# uoolight.net
KiCad netlist of a schematic drawn in EAGLE
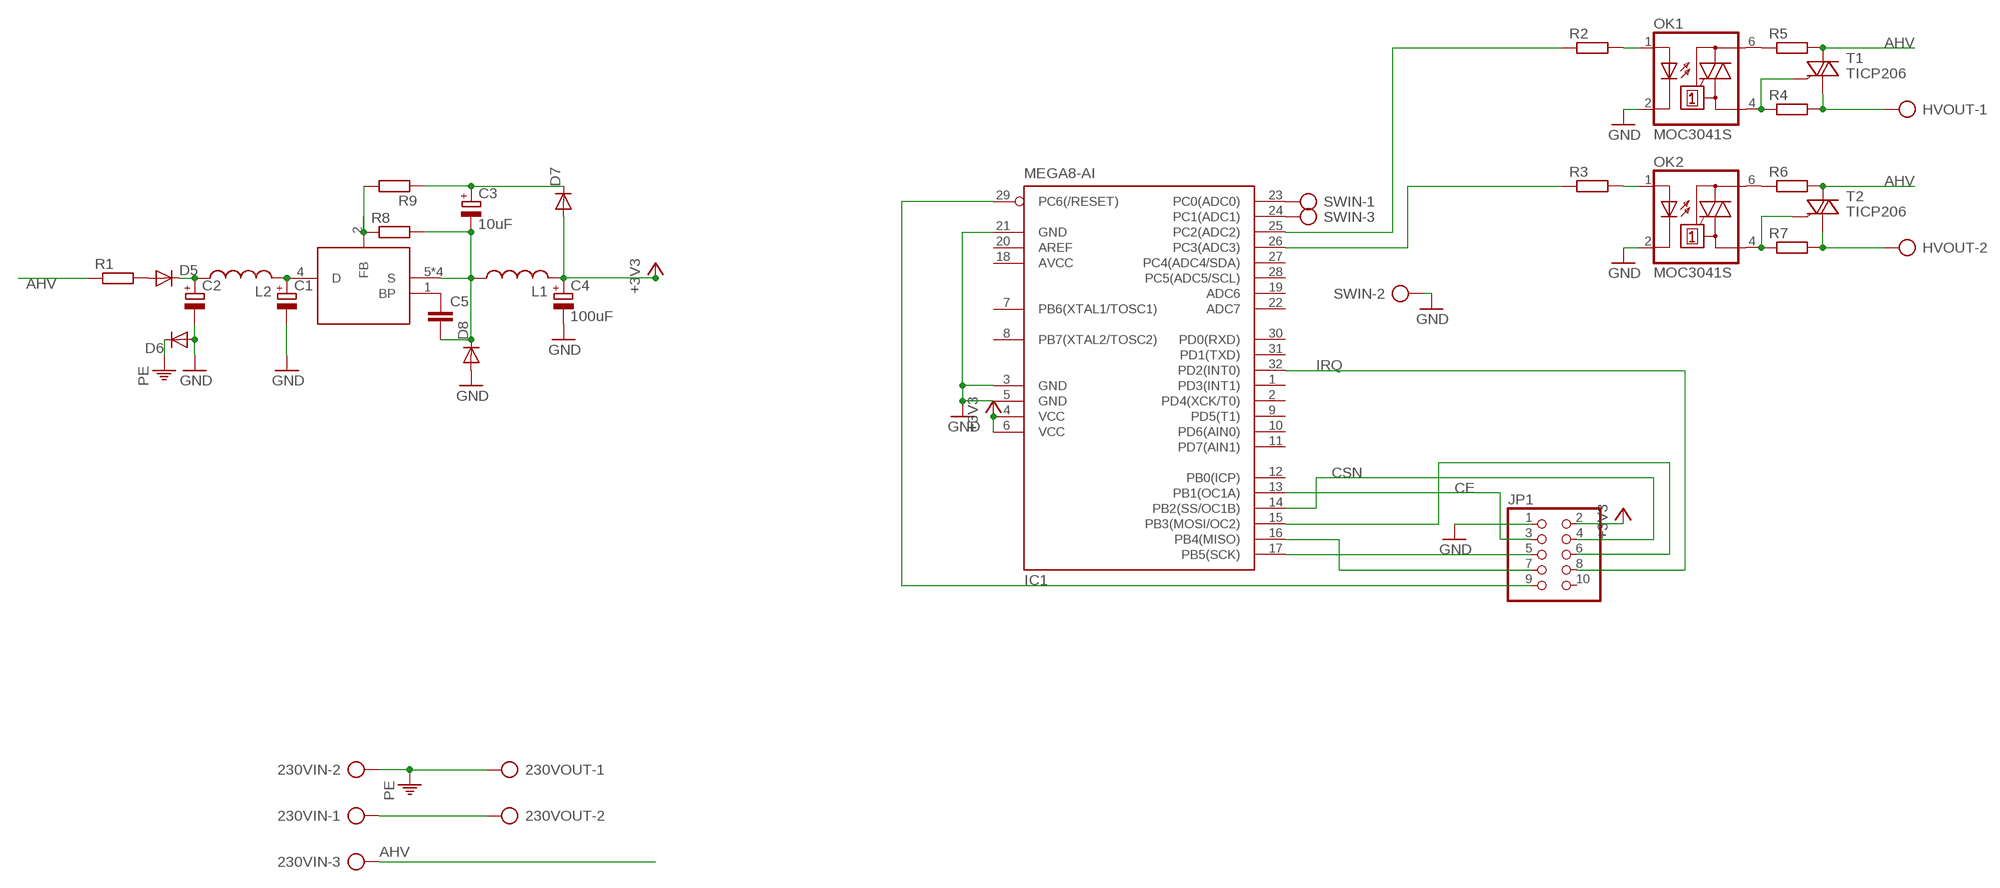
[diagram p0: schematic, sheet 1]

(export (version "E")
  (design (tool "Eeschema 10.0.6"))
  (components
    (comp (ref "230VIN")
      (value "AK500/3")
      (footprint "eagle-import:AK500_3")
      (libsource (lib "eagle-import") (part "AK500/3"))
    )
    (comp (ref "230VOUT")
      (value "AK500/2")
      (footprint "eagle-import:AK500_2")
      (libsource (lib "eagle-import") (part "AK500/2"))
    )
    (comp (ref "C1")
      (value "CPOL-EUE5-10.5")
      (footprint "eagle-import:E5-10,5")
      (libsource (lib "eagle-import") (part "CPOL-EUE5-10.5"))
    )
    (comp (ref "C2")
      (value "CPOL-EUE5-10.5")
      (footprint "eagle-import:E5-10,5")
      (libsource (lib "eagle-import") (part "CPOL-EUE5-10.5"))
    )
    (comp (ref "C3")
      (value "10uF")
      (footprint "eagle-import:153CLV-0505")
      (libsource (lib "eagle-import") (part "CPOL-EU153CLV-0505"))
    )
    (comp (ref "C4")
      (value "100uF")
      (footprint "eagle-import:153CLV-0605")
      (libsource (lib "eagle-import") (part "CPOL-EU153CLV-0605"))
    )
    (comp (ref "C5")
      (value "C-EUC0603K")
      (footprint "eagle-import:C0603K")
      (libsource (lib "eagle-import") (part "C-EUC0603K"))
    )
    (comp (ref "D5")
      (value "DIODE-SOD323-W")
      (footprint "eagle-import:SOD323-W")
      (libsource (lib "eagle-import") (part "DIODE-SOD323-W"))
    )
    (comp (ref "D6")
      (value "DIODE-SOD323-W")
      (footprint "eagle-import:SOD323-W")
      (libsource (lib "eagle-import") (part "DIODE-SOD323-W"))
    )
    (comp (ref "D7")
      (value "DIODE-SOD323-W")
      (footprint "eagle-import:SOD323-W")
      (libsource (lib "eagle-import") (part "DIODE-SOD323-W"))
    )
    (comp (ref "D8")
      (value "DIODE-SOD123")
      (footprint "eagle-import:SOD123")
      (libsource (lib "eagle-import") (part "DIODE-SOD123"))
    )
    (comp (ref "HVOUT")
      (value "AK500/2")
      (footprint "eagle-import:AK500_2")
      (libsource (lib "eagle-import") (part "AK500/2"))
    )
    (comp (ref "IC1")
      (value "MEGA8-AI")
      (footprint "eagle-import:TQFP32-08")
      (fields (field (name "MPN") "ATMEGA8-16AU"))
      (libsource (lib "eagle-import") (part "MEGA8-AI"))
    )
    (comp (ref "JP1")
      (value "PINHD-2X5")
      (footprint "eagle-import:2X05")
      (libsource (lib "eagle-import") (part "PINHD-2X5"))
    )
    (comp (ref "L1")
      (value "L-USPIS2816")
      (footprint "eagle-import:PIS2816")
      (libsource (lib "eagle-import") (part "L-USPIS2816"))
    )
    (comp (ref "L2")
      (value "L-USPIS2816")
      (footprint "eagle-import:PIS2816")
      (libsource (lib "eagle-import") (part "L-USPIS2816"))
    )
    (comp (ref "OK1")
      (value "MOC3041S")
      (footprint "eagle-import:DIL6-SMD")
      (fields (field (name "MF") "FAIRCHILD SEMICONDUCTOR") (field (name "MPN") "MOC3041S-M"))
      (libsource (lib "eagle-import") (part "MOC30S41"))
    )
    (comp (ref "OK2")
      (value "MOC3041S")
      (footprint "eagle-import:DIL6-SMD")
      (fields (field (name "MF") "FAIRCHILD SEMICONDUCTOR") (field (name "MPN") "MOC3041S-M"))
      (libsource (lib "eagle-import") (part "MOC30S41"))
    )
    (comp (ref "R1")
      (value "R-EU_0309/12")
      (footprint "eagle-import:0309_12")
      (libsource (lib "eagle-import") (part "R-EU_0309/12"))
    )
    (comp (ref "R2")
      (value "R-EU_R0805")
      (footprint "eagle-import:R0805")
      (libsource (lib "eagle-import") (part "R-EU_R0805"))
    )
    (comp (ref "R3")
      (value "R-EU_R0805")
      (footprint "eagle-import:R0805")
      (libsource (lib "eagle-import") (part "R-EU_R0805"))
    )
    (comp (ref "R4")
      (value "R-EU_R0805")
      (footprint "eagle-import:R0805")
      (libsource (lib "eagle-import") (part "R-EU_R0805"))
    )
    (comp (ref "R5")
      (value "R-EU_R0805")
      (footprint "eagle-import:R0805")
      (libsource (lib "eagle-import") (part "R-EU_R0805"))
    )
    (comp (ref "R6")
      (value "R-EU_R0805")
      (footprint "eagle-import:R0805")
      (libsource (lib "eagle-import") (part "R-EU_R0805"))
    )
    (comp (ref "R7")
      (value "R-EU_R0805")
      (footprint "eagle-import:R0805")
      (libsource (lib "eagle-import") (part "R-EU_R0805"))
    )
    (comp (ref "R8")
      (value "R-EU_R0805")
      (footprint "eagle-import:R0805")
      (libsource (lib "eagle-import") (part "R-EU_R0805"))
    )
    (comp (ref "R9")
      (value "R-EU_R0805")
      (footprint "eagle-import:R0805")
      (libsource (lib "eagle-import") (part "R-EU_R0805"))
    )
    (comp (ref "SWIN")
      (value "AK500/3")
      (footprint "eagle-import:AK500_3")
      (libsource (lib "eagle-import") (part "AK500/3"))
    )
    (comp (ref "T1")
      (value "TICP206")
      (footprint "eagle-import:TO92-6")
      (libsource (lib "eagle-import") (part "TICP206"))
    )
    (comp (ref "T2")
      (value "TICP206")
      (footprint "eagle-import:TO92-6")
      (libsource (lib "eagle-import") (part "TICP206"))
    )
    (comp (ref "U$1")
      (value "LNK304")
      (footprint "eagle-import:SO8(SO-8C)")
      (libsource (lib "eagle-import") (part "LNK304"))
    )
  )
  (nets
    (net (code "1") (name "+3V3") (class "Default")
      (node (ref "C4") (pin "+") (pinfunction "+_+") (pintype "passive"))
      (node (ref "D7") (pin "A") (pinfunction "A_A") (pintype "passive"))
      (node (ref "IC1") (pin "4") (pinfunction "VCC_4") (pintype "power_in"))
      (node (ref "IC1") (pin "6") (pinfunction "VCC_6") (pintype "power_in"))
      (node (ref "JP1") (pin "2") (pinfunction "2_2") (pintype "passive"))
      (node (ref "L1") (pin "2") (pinfunction "2_2") (pintype "passive"))
    )
    (net (code "2") (name "/AHV") (class "Default")
      (node (ref "230VIN") (pin "3") (pinfunction "KL_3") (pintype "passive"))
      (node (ref "R1") (pin "1") (pinfunction "1_1") (pintype "passive"))
      (node (ref "R5") (pin "2") (pinfunction "2_2") (pintype "passive"))
      (node (ref "R6") (pin "2") (pinfunction "2_2") (pintype "passive"))
      (node (ref "T1") (pin "A2") (pinfunction "A2_A2") (pintype "passive"))
      (node (ref "T2") (pin "A2") (pinfunction "A2_A2") (pintype "passive"))
    )
    (net (code "3") (name "/AVCC") (class "Default")
      (node (ref "IC1") (pin "18") (pinfunction "AVCC_18") (pintype "power_in"))
    )
    (net (code "4") (name "/CE") (class "Default")
      (node (ref "IC1") (pin "13") (pinfunction "PB1(OC1A)_13") (pintype "bidirectional"))
      (node (ref "JP1") (pin "3") (pinfunction "3_3") (pintype "passive"))
    )
    (net (code "5") (name "/CSN") (class "Default")
      (node (ref "IC1") (pin "14") (pinfunction "PB2(SS/OC1B)_14") (pintype "bidirectional"))
      (node (ref "JP1") (pin "4") (pinfunction "4_4") (pintype "passive"))
    )
    (net (code "6") (name "/IRQ") (class "Default")
      (node (ref "IC1") (pin "32") (pinfunction "PD2(INT0)_32") (pintype "bidirectional"))
      (node (ref "JP1") (pin "8") (pinfunction "8_8") (pintype "passive"))
    )
    (net (code "7") (name "GND") (class "Default")
      (node (ref "C1") (pin "-") (pinfunction "-_-") (pintype "passive"))
      (node (ref "C2") (pin "-") (pinfunction "-_-") (pintype "passive"))
      (node (ref "C4") (pin "-") (pinfunction "-_-") (pintype "passive"))
      (node (ref "D6") (pin "A") (pinfunction "A_A") (pintype "passive"))
      (node (ref "D8") (pin "A") (pinfunction "A_A") (pintype "passive"))
      (node (ref "IC1") (pin "21") (pinfunction "GND_21") (pintype "power_in"))
      (node (ref "IC1") (pin "3") (pinfunction "GND_3") (pintype "power_in"))
      (node (ref "IC1") (pin "5") (pinfunction "GND_5") (pintype "power_in"))
      (node (ref "JP1") (pin "1") (pinfunction "1_1") (pintype "passive"))
      (node (ref "OK1") (pin "2") (pinfunction "C_2") (pintype "passive"))
      (node (ref "OK2") (pin "2") (pinfunction "C_2") (pintype "passive"))
      (node (ref "SWIN") (pin "2") (pinfunction "KL_2") (pintype "passive"))
    )
    (net (code "8") (name "Net-(230VINA-KL)") (class "Default")
      (node (ref "230VIN") (pin "1") (pinfunction "KL_1") (pintype "passive"))
      (node (ref "230VOUT") (pin "2") (pinfunction "KL_2") (pintype "passive"))
    )
    (net (code "9") (name "Net-(C2-Pad+)") (class "Default")
      (node (ref "C2") (pin "+") (pinfunction "+_+") (pintype "passive"))
      (node (ref "D5") (pin "C") (pinfunction "C_C") (pintype "passive"))
      (node (ref "L2") (pin "1") (pinfunction "1_1") (pintype "passive"))
    )
    (net (code "10") (name "Net-(C3-Pad+)") (class "Default")
      (node (ref "C3") (pin "+") (pinfunction "+_+") (pintype "passive"))
      (node (ref "D7") (pin "C") (pinfunction "C_C") (pintype "passive"))
      (node (ref "R9") (pin "1") (pinfunction "1_1") (pintype "passive"))
    )
    (net (code "11") (name "Net-(C3-Pad-)") (class "Default")
      (node (ref "C3") (pin "-") (pinfunction "-_-") (pintype "passive"))
      (node (ref "C5") (pin "2") (pinfunction "2_2") (pintype "passive"))
      (node (ref "D8") (pin "C") (pinfunction "C_C") (pintype "passive"))
      (node (ref "L1") (pin "1") (pinfunction "1_1") (pintype "passive"))
      (node (ref "R8") (pin "2") (pinfunction "2_2") (pintype "passive"))
      (node (ref "U$1") (pin "5") (pinfunction "S_5") (pintype "bidirectional"))
      (node (ref "U$1") (pin "6") (pinfunction "S_6") (pintype "bidirectional"))
      (node (ref "U$1") (pin "7") (pinfunction "S_7") (pintype "bidirectional"))
      (node (ref "U$1") (pin "8") (pinfunction "S_8") (pintype "bidirectional"))
    )
    (net (code "12") (name "Net-(D5-PadA)") (class "Default")
      (node (ref "D5") (pin "A") (pinfunction "A_A") (pintype "passive"))
      (node (ref "R1") (pin "2") (pinfunction "2_2") (pintype "passive"))
    )
    (net (code "13") (name "Net-(HVOUTA-KL)") (class "Default")
      (node (ref "HVOUT") (pin "1") (pinfunction "KL_1") (pintype "passive"))
      (node (ref "R4") (pin "2") (pinfunction "2_2") (pintype "passive"))
      (node (ref "T1") (pin "A1") (pinfunction "A1_A1") (pintype "passive"))
    )
    (net (code "14") (name "Net-(HVOUTB-KL)") (class "Default")
      (node (ref "HVOUT") (pin "2") (pinfunction "KL_2") (pintype "passive"))
      (node (ref "R7") (pin "2") (pinfunction "2_2") (pintype "passive"))
      (node (ref "T2") (pin "A1") (pinfunction "A1_A1") (pintype "passive"))
    )
    (net (code "15") (name "Net-(IC1-PB3(MOSI{slash}OC2))") (class "Default")
      (node (ref "IC1") (pin "15") (pinfunction "PB3(MOSI/OC2)_15") (pintype "bidirectional"))
      (node (ref "JP1") (pin "6") (pinfunction "6_6") (pintype "passive"))
    )
    (net (code "16") (name "Net-(IC1-PB4(MISO))") (class "Default")
      (node (ref "IC1") (pin "16") (pinfunction "PB4(MISO)_16") (pintype "bidirectional"))
      (node (ref "JP1") (pin "7") (pinfunction "7_7") (pintype "passive"))
    )
    (net (code "17") (name "Net-(IC1-PB5(SCK))") (class "Default")
      (node (ref "IC1") (pin "17") (pinfunction "PB5(SCK)_17") (pintype "bidirectional"))
      (node (ref "JP1") (pin "5") (pinfunction "5_5") (pintype "passive"))
    )
    (net (code "18") (name "Net-(IC1-PC0(ADC0))") (class "Default")
      (node (ref "IC1") (pin "23") (pinfunction "PC0(ADC0)_23") (pintype "bidirectional"))
      (node (ref "SWIN") (pin "1") (pinfunction "KL_1") (pintype "passive"))
    )
    (net (code "19") (name "Net-(IC1-PC1(ADC1))") (class "Default")
      (node (ref "IC1") (pin "24") (pinfunction "PC1(ADC1)_24") (pintype "bidirectional"))
      (node (ref "SWIN") (pin "3") (pinfunction "KL_3") (pintype "passive"))
    )
    (net (code "20") (name "Net-(IC1-PC2(ADC2))") (class "Default")
      (node (ref "IC1") (pin "25") (pinfunction "PC2(ADC2)_25") (pintype "bidirectional"))
      (node (ref "R2") (pin "1") (pinfunction "1_1") (pintype "passive"))
    )
    (net (code "21") (name "Net-(IC1-PC3(ADC3))") (class "Default")
      (node (ref "IC1") (pin "26") (pinfunction "PC3(ADC3)_26") (pintype "bidirectional"))
      (node (ref "R3") (pin "1") (pinfunction "1_1") (pintype "passive"))
    )
    (net (code "22") (name "Net-(IC1-PC6({slash}RESET))") (class "Default")
      (node (ref "IC1") (pin "29") (pinfunction "PC6(/RESET)_29") (pintype "bidirectional"))
      (node (ref "JP1") (pin "9") (pinfunction "9_9") (pintype "passive"))
    )
    (net (code "23") (name "Net-(OK1-A)") (class "Default")
      (node (ref "OK1") (pin "1") (pinfunction "A_1") (pintype "passive"))
      (node (ref "R2") (pin "2") (pinfunction "2_2") (pintype "passive"))
    )
    (net (code "24") (name "Net-(OK1-A1)") (class "Default")
      (node (ref "OK1") (pin "4") (pinfunction "A1_4") (pintype "passive"))
      (node (ref "R4") (pin "1") (pinfunction "1_1") (pintype "passive"))
      (node (ref "T1") (pin "G") (pinfunction "G_G") (pintype "passive"))
    )
    (net (code "25") (name "Net-(OK1-A2)") (class "Default")
      (node (ref "OK1") (pin "6") (pinfunction "A2_6") (pintype "passive"))
      (node (ref "R5") (pin "1") (pinfunction "1_1") (pintype "passive"))
    )
    (net (code "26") (name "Net-(OK2-A)") (class "Default")
      (node (ref "OK2") (pin "1") (pinfunction "A_1") (pintype "passive"))
      (node (ref "R3") (pin "2") (pinfunction "2_2") (pintype "passive"))
    )
    (net (code "27") (name "Net-(OK2-A1)") (class "Default")
      (node (ref "OK2") (pin "4") (pinfunction "A1_4") (pintype "passive"))
      (node (ref "R7") (pin "1") (pinfunction "1_1") (pintype "passive"))
      (node (ref "T2") (pin "G") (pinfunction "G_G") (pintype "passive"))
    )
    (net (code "28") (name "Net-(OK2-A2)") (class "Default")
      (node (ref "OK2") (pin "6") (pinfunction "A2_6") (pintype "passive"))
      (node (ref "R6") (pin "1") (pinfunction "1_1") (pintype "passive"))
    )
    (net (code "29") (name "Net-(U$1-BP)") (class "Default")
      (node (ref "C5") (pin "1") (pinfunction "1_1") (pintype "passive"))
      (node (ref "U$1") (pin "1") (pinfunction "BP_1") (pintype "bidirectional"))
    )
    (net (code "30") (name "Net-(U$1-D)") (class "Default")
      (node (ref "C1") (pin "+") (pinfunction "+_+") (pintype "passive"))
      (node (ref "L2") (pin "2") (pinfunction "2_2") (pintype "passive"))
      (node (ref "U$1") (pin "4") (pinfunction "D_4") (pintype "bidirectional"))
    )
    (net (code "31") (name "Net-(U$1-FB)") (class "Default")
      (node (ref "R8") (pin "1") (pinfunction "1_1") (pintype "passive"))
      (node (ref "R9") (pin "2") (pinfunction "2_2") (pintype "passive"))
      (node (ref "U$1") (pin "2") (pinfunction "FB_2") (pintype "bidirectional"))
    )
    (net (code "32") (name "PE") (class "Default")
      (node (ref "230VIN") (pin "2") (pinfunction "KL_2") (pintype "passive"))
      (node (ref "230VOUT") (pin "1") (pinfunction "KL_1") (pintype "passive"))
      (node (ref "D6") (pin "C") (pinfunction "C_C") (pintype "passive"))
    )
    (net (code "33") (name "unconnected-(IC1-ADC6-Pad19)") (class "Default")
      (node (ref "IC1") (pin "19") (pinfunction "ADC6_19") (pintype "bidirectional"))
    )
    (net (code "34") (name "unconnected-(IC1-ADC7-Pad22)") (class "Default")
      (node (ref "IC1") (pin "22") (pinfunction "ADC7_22") (pintype "bidirectional"))
    )
    (net (code "35") (name "unconnected-(IC1-AREF-Pad20)") (class "Default")
      (node (ref "IC1") (pin "20") (pinfunction "AREF_20") (pintype "passive"))
    )
    (net (code "36") (name "unconnected-(IC1-PB0(ICP)-Pad12)") (class "Default")
      (node (ref "IC1") (pin "12") (pinfunction "PB0(ICP)_12") (pintype "bidirectional"))
    )
    (net (code "37") (name "unconnected-(IC1-PB6(XTAL1{slash}TOSC1)-Pad7)") (class "Default")
      (node (ref "IC1") (pin "7") (pinfunction "PB6(XTAL1/TOSC1)_7") (pintype "bidirectional"))
    )
    (net (code "38") (name "unconnected-(IC1-PB7(XTAL2{slash}TOSC2)-Pad8)") (class "Default")
      (node (ref "IC1") (pin "8") (pinfunction "PB7(XTAL2/TOSC2)_8") (pintype "bidirectional"))
    )
    (net (code "39") (name "unconnected-(IC1-PC4(ADC4{slash}SDA)-Pad27)") (class "Default")
      (node (ref "IC1") (pin "27") (pinfunction "PC4(ADC4/SDA)_27") (pintype "bidirectional"))
    )
    (net (code "40") (name "unconnected-(IC1-PC5(ADC5{slash}SCL)-Pad28)") (class "Default")
      (node (ref "IC1") (pin "28") (pinfunction "PC5(ADC5/SCL)_28") (pintype "bidirectional"))
    )
    (net (code "41") (name "unconnected-(IC1-PD0(RXD)-Pad30)") (class "Default")
      (node (ref "IC1") (pin "30") (pinfunction "PD0(RXD)_30") (pintype "bidirectional"))
    )
    (net (code "42") (name "unconnected-(IC1-PD1(TXD)-Pad31)") (class "Default")
      (node (ref "IC1") (pin "31") (pinfunction "PD1(TXD)_31") (pintype "bidirectional"))
    )
    (net (code "43") (name "unconnected-(IC1-PD3(INT1)-Pad1)") (class "Default")
      (node (ref "IC1") (pin "1") (pinfunction "PD3(INT1)_1") (pintype "bidirectional"))
    )
    (net (code "44") (name "unconnected-(IC1-PD4(XCK{slash}T0)-Pad2)") (class "Default")
      (node (ref "IC1") (pin "2") (pinfunction "PD4(XCK/T0)_2") (pintype "bidirectional"))
    )
    (net (code "45") (name "unconnected-(IC1-PD5(T1)-Pad9)") (class "Default")
      (node (ref "IC1") (pin "9") (pinfunction "PD5(T1)_9") (pintype "bidirectional"))
    )
    (net (code "46") (name "unconnected-(IC1-PD6(AIN0)-Pad10)") (class "Default")
      (node (ref "IC1") (pin "10") (pinfunction "PD6(AIN0)_10") (pintype "bidirectional"))
    )
    (net (code "47") (name "unconnected-(IC1-PD7(AIN1)-Pad11)") (class "Default")
      (node (ref "IC1") (pin "11") (pinfunction "PD7(AIN1)_11") (pintype "bidirectional"))
    )
    (net (code "48") (name "unconnected-(JP1-Pad10)") (class "Default")
      (node (ref "JP1") (pin "10") (pinfunction "10_10") (pintype "passive"))
    )
  )
)
